# Adafruit_PA1010D_Mini_GPS.net
KiCad netlist of a schematic drawn in Altium Designer
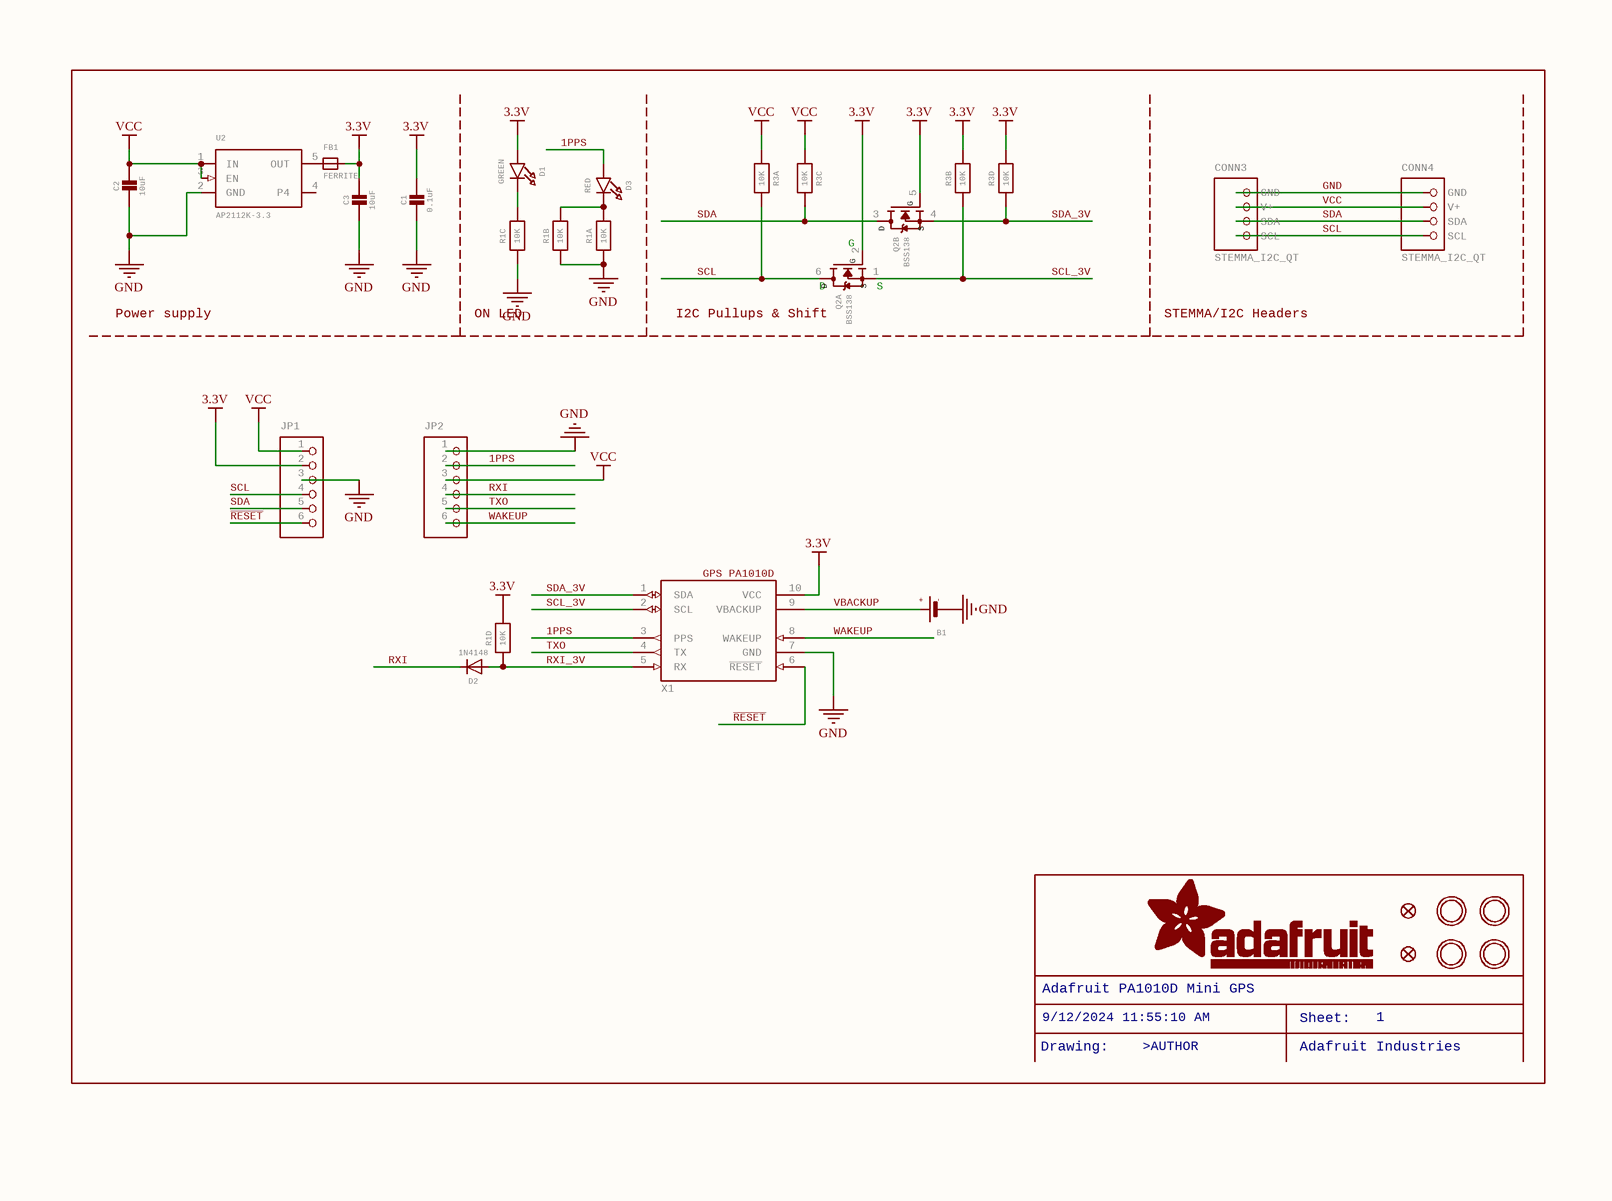
[diagram p0: Adafruit PA1010D Mini GPS.SchDoc]

(export (version "E")
  (design (tool "Eeschema 10.0.6"))
  (components
    (comp (ref "B1")
      (value "BATTERYCR1220_2")
      (footprint "CR1220-2")
      (description "CR1220 SMT - Digikey: 3001K-ND  CD2032 BAT-HLD-001 - Digikey: BAT-HLD-001-ND")
      (fields (field (name "+") "+") (field (name "-") "-"))
      (libsource (lib "microbuilder") (part "BATTERYCR1220_2"))
    )
    (comp (ref "C1")
      (value "0.1uF")
      (footprint "0603-NO")
      (libsource (lib "microbuilder") (part "CAP_CERAMIC0603_NO"))
    )
    (comp (ref "C2")
      (value "10uF")
      (footprint "0805-NO")
      (libsource (lib "microbuilder") (part "CAP_CERAMIC0805-NOOUTLINE"))
    )
    (comp (ref "C3")
      (value "10uF")
      (footprint "0805-NO")
      (libsource (lib "microbuilder") (part "CAP_CERAMIC0805-NOOUTLINE"))
    )
    (comp (ref "CONN3")
      (value "STEMMA_I2C_QT")
      (footprint "JST_SH4")
      (libsource (lib "microbuilder") (part "STEMMA_I2C_QT"))
    )
    (comp (ref "CONN4")
      (value "STEMMA_I2C_QT")
      (footprint "JST_SH4")
      (libsource (lib "microbuilder") (part "STEMMA_I2C_QT"))
    )
    (comp (ref "D1")
      (value "GREEN")
      (footprint "CHIPLED_0603_NOOUTLINE")
      (libsource (lib "microbuilder") (part "LED0603_NOOUTLINE"))
    )
    (comp (ref "D2")
      (value "1N4148")
      (footprint "SOD-323")
      (libsource (lib "microbuilder") (part "DIODESOD-323"))
    )
    (comp (ref "D3")
      (value "RED")
      (footprint "CHIPLED_0603_NOOUTLINE")
      (libsource (lib "microbuilder") (part "LED0603_NOOUTLINE"))
    )
    (comp (ref "FB1")
      (value "FERRITE")
      (footprint "0805-NO")
      (libsource (lib "microbuilder") (part "FERRITE-0805NO"))
    )
    (comp (ref "FID3")
      (value "FIDUCIAL_1MM")
      (footprint "FIDUCIAL_1MM")
      (description "Fiducial Alignment Points   Various fiducial points for machine vision alignment.")
      (libsource (lib "microbuilder") (part "FIDUCIAL_1MM"))
    )
    (comp (ref "FID4")
      (value "FIDUCIAL_1MM")
      (footprint "FIDUCIAL_1MM")
      (description "Fiducial Alignment Points   Various fiducial points for machine vision alignment.")
      (libsource (lib "microbuilder") (part "FIDUCIAL_1MM"))
    )
    (comp (ref "JP1")
      (value "HEADER-1X670MIL")
      (footprint "1X06_ROUND_70")
      (description "PIN HEADER")
      (libsource (lib "microbuilder") (part "HEADER-1X670MIL"))
    )
    (comp (ref "JP2")
      (value "HEADER-1X670MIL")
      (footprint "1X06_ROUND_70")
      (description "PIN HEADER")
      (libsource (lib "microbuilder") (part "HEADER-1X670MIL"))
    )
    (comp (ref "Q2")
      (value "BSS138")
      (footprint "SOT363")
      (description "Dual N-Channel MOSFET   SOT363 (2.0x1.25mm) 2N7002PS - 60V, 320mA [Digikey: 568-5984-1-ND]")
      (fields (field (name "D") "D") (field (name "S") "S") (field (name "G") "G"))
      (libsource (lib "microbuilder") (part "MOSFET-N_DUAL"))
    )
    (comp (ref "R1")
      (value "10K")
      (footprint "RESPACK_4X0603")
      (description "Resistor Packs (4 resistors)   4 x 0603 10K 1/16W - Digikey: YC164J-10KCT-ND")
      (libsource (lib "microbuilder") (part "RESISTOR_4PACK"))
    )
    (comp (ref "R3")
      (value "10K")
      (footprint "RESPACK_4X0603")
      (description "Resistor Packs (4 resistors)   4 x 0603 10K 1/16W - Digikey: YC164J-10KCT-ND")
      (libsource (lib "microbuilder") (part "RESISTOR_4PACK"))
    )
    (comp (ref "U$1")
      (value "MOUNTINGHOLE2.5")
      (footprint "MOUNTINGHOLE_2.5_PLATED")
      (description "Mounting Hole   For #2 screws (0.086\"/2.18mm width, 0.094\"/2.4mm hole) use 2.5mm")
      (libsource (lib "microbuilder") (part "MOUNTINGHOLE2.5"))
    )
    (comp (ref "U$17")
      (value "MOUNTINGHOLE2.5")
      (footprint "MOUNTINGHOLE_2.5_PLATED")
      (description "Mounting Hole   For #2 screws (0.086\"/2.18mm width, 0.094\"/2.4mm hole) use 2.5mm")
      (libsource (lib "microbuilder") (part "MOUNTINGHOLE2.5"))
    )
    (comp (ref "U$19")
      (value "MOUNTINGHOLE2.5")
      (footprint "MOUNTINGHOLE_2.5_PLATED")
      (description "Mounting Hole   For #2 screws (0.086\"/2.18mm width, 0.094\"/2.4mm hole) use 2.5mm")
      (libsource (lib "microbuilder") (part "MOUNTINGHOLE2.5"))
    )
    (comp (ref "U$21")
      (value "MOUNTINGHOLE2.5")
      (footprint "MOUNTINGHOLE_2.5_PLATED")
      (description "Mounting Hole   For #2 screws (0.086\"/2.18mm width, 0.094\"/2.4mm hole) use 2.5mm")
      (libsource (lib "microbuilder") (part "MOUNTINGHOLE2.5"))
    )
    (comp (ref "U2")
      (value "AP2112K-3.3")
      (footprint "SOT23-5")
      (libsource (lib "microbuilder") (part "VREG_SOT23-5"))
    )
    (comp (ref "X1")
      (value "GPS_PA1010D")
      (footprint "GPS_PA1010D")
      (fields (field (name "GPSPA1010D") "GPS PA1010D"))
      (libsource (lib "microbuilder") (part "GPS_PA1010D"))
    )
  )
  (nets
    (net (code "1") (name "/1PPS") (class "Default")
      (node (ref "D3") (pin "A") (pinfunction "A_A") (pintype "passive"))
      (node (ref "JP2") (pin "2") (pinfunction "2_2") (pintype "passive"))
      (node (ref "X1") (pin "3") (pinfunction "PPS_3") (pintype "output"))
    )
    (net (code "2") (name "/RXI") (class "Default")
      (node (ref "D2") (pin "C") (pinfunction "C_C") (pintype "passive"))
      (node (ref "JP2") (pin "4") (pinfunction "4_4") (pintype "passive"))
    )
    (net (code "3") (name "/RXI_3V") (class "Default")
      (node (ref "D2") (pin "A") (pinfunction "A_A") (pintype "passive"))
      (node (ref "R1") (pin "5") (pinfunction "2_5") (pintype "passive"))
      (node (ref "X1") (pin "5") (pinfunction "RX_5") (pintype "input"))
    )
    (net (code "4") (name "/SCL") (class "Default")
      (node (ref "CONN3") (pin "4") (pinfunction "SCL_4") (pintype "passive"))
      (node (ref "CONN4") (pin "4") (pinfunction "SCL_4") (pintype "passive"))
      (node (ref "JP1") (pin "4") (pinfunction "4_4") (pintype "passive"))
      (node (ref "Q2") (pin "6") (pinfunction "D_6") (pintype "bidirectional"))
      (node (ref "R3") (pin "8") (pinfunction "2_8") (pintype "passive"))
    )
    (net (code "5") (name "/SCL_3V") (class "Default")
      (node (ref "Q2") (pin "1") (pinfunction "S_1") (pintype "bidirectional"))
      (node (ref "R3") (pin "7") (pinfunction "2_7") (pintype "passive"))
      (node (ref "X1") (pin "2") (pinfunction "SCL_2") (pintype "bidirectional"))
    )
    (net (code "6") (name "/SDA") (class "Default")
      (node (ref "CONN3") (pin "3") (pinfunction "SDA_3") (pintype "passive"))
      (node (ref "CONN4") (pin "3") (pinfunction "SDA_3") (pintype "passive"))
      (node (ref "JP1") (pin "5") (pinfunction "5_5") (pintype "passive"))
      (node (ref "Q2") (pin "3") (pinfunction "D_3") (pintype "bidirectional"))
      (node (ref "R3") (pin "6") (pinfunction "2_6") (pintype "passive"))
    )
    (net (code "7") (name "/SDA_3V") (class "Default")
      (node (ref "Q2") (pin "4") (pinfunction "S_4") (pintype "bidirectional"))
      (node (ref "R3") (pin "5") (pinfunction "2_5") (pintype "passive"))
      (node (ref "X1") (pin "1") (pinfunction "SDA_1") (pintype "bidirectional"))
    )
    (net (code "8") (name "/TXO") (class "Default")
      (node (ref "JP2") (pin "5") (pinfunction "5_5") (pintype "passive"))
      (node (ref "X1") (pin "4") (pinfunction "TX_4") (pintype "output"))
    )
    (net (code "9") (name "/VBACKUP") (class "Default")
      (node (ref "B1") (pin "+") (pinfunction "+_+") (pintype "passive"))
      (node (ref "X1") (pin "9") (pinfunction "VBACKUP_9") (pintype "power_in"))
    )
    (net (code "10") (name "/WAKEUP") (class "Default")
      (node (ref "JP2") (pin "6") (pinfunction "6_6") (pintype "passive"))
      (node (ref "X1") (pin "8") (pinfunction "WAKEUP_8") (pintype "input"))
    )
    (net (code "11") (name "/~{RESET}") (class "Default")
      (node (ref "JP1") (pin "6") (pinfunction "6_6") (pintype "passive"))
      (node (ref "X1") (pin "6") (pinfunction "~{RESET}_6") (pintype "input"))
    )
    (net (code "12") (name "3.3V") (class "Default")
      (node (ref "C1") (pin "1") (pinfunction "1_1") (pintype "passive"))
      (node (ref "C3") (pin "1") (pinfunction "1_1") (pintype "passive"))
      (node (ref "D1") (pin "A") (pinfunction "A_A") (pintype "passive"))
      (node (ref "FB1") (pin "2") (pinfunction "P$2_2") (pintype "passive"))
      (node (ref "JP1") (pin "2") (pinfunction "2_2") (pintype "passive"))
      (node (ref "Q2") (pin "2") (pinfunction "G_2") (pintype "bidirectional"))
      (node (ref "Q2") (pin "5") (pinfunction "G_5") (pintype "bidirectional"))
      (node (ref "R1") (pin "4") (pinfunction "1_4") (pintype "passive"))
      (node (ref "R3") (pin "2") (pinfunction "1_2") (pintype "passive"))
      (node (ref "R3") (pin "4") (pinfunction "1_4") (pintype "passive"))
      (node (ref "X1") (pin "10") (pinfunction "VCC_10") (pintype "power_in"))
    )
    (net (code "13") (name "GND") (class "Default")
      (node (ref "B1") (pin "-") (pinfunction "-_-") (pintype "passive"))
      (node (ref "C1") (pin "2") (pinfunction "2_2") (pintype "passive"))
      (node (ref "C2") (pin "2") (pinfunction "2_2") (pintype "passive"))
      (node (ref "C3") (pin "2") (pinfunction "2_2") (pintype "passive"))
      (node (ref "CONN3") (pin "1") (pinfunction "GND_1") (pintype "passive"))
      (node (ref "CONN4") (pin "1") (pinfunction "GND_1") (pintype "passive"))
      (node (ref "JP1") (pin "3") (pinfunction "3_3") (pintype "passive"))
      (node (ref "JP2") (pin "1") (pinfunction "1_1") (pintype "passive"))
      (node (ref "R1") (pin "1") (pinfunction "1_1") (pintype "passive"))
      (node (ref "R1") (pin "2") (pinfunction "1_2") (pintype "passive"))
      (node (ref "R1") (pin "3") (pinfunction "1_3") (pintype "passive"))
      (node (ref "U2") (pin "2") (pinfunction "GND_2") (pintype "power_in"))
      (node (ref "X1") (pin "7") (pinfunction "GND_7") (pintype "power_in"))
    )
    (net (code "14") (name "Net-(FB1-P$1)") (class "Default")
      (node (ref "FB1") (pin "1") (pinfunction "P$1_1") (pintype "passive"))
      (node (ref "U2") (pin "5") (pinfunction "OUT_5") (pintype "power_in"))
    )
    (net (code "15") (name "Net-(R1A-2)") (class "Default")
      (node (ref "D3") (pin "C") (pinfunction "C_C") (pintype "passive"))
      (node (ref "R1") (pin "7") (pinfunction "2_7") (pintype "passive"))
      (node (ref "R1") (pin "8") (pinfunction "2_8") (pintype "passive"))
    )
    (net (code "16") (name "Net-(R1C-2)") (class "Default")
      (node (ref "D1") (pin "C") (pinfunction "C_C") (pintype "passive"))
      (node (ref "R1") (pin "6") (pinfunction "2_6") (pintype "passive"))
    )
    (net (code "17") (name "VCC") (class "Default")
      (node (ref "C2") (pin "1") (pinfunction "1_1") (pintype "passive"))
      (node (ref "CONN3") (pin "2") (pinfunction "V+_2") (pintype "passive"))
      (node (ref "CONN4") (pin "2") (pinfunction "V+_2") (pintype "passive"))
      (node (ref "JP1") (pin "1") (pinfunction "1_1") (pintype "passive"))
      (node (ref "JP2") (pin "3") (pinfunction "3_3") (pintype "passive"))
      (node (ref "R3") (pin "1") (pinfunction "1_1") (pintype "passive"))
      (node (ref "R3") (pin "3") (pinfunction "1_3") (pintype "passive"))
      (node (ref "U2") (pin "1") (pinfunction "IN_1") (pintype "power_in"))
      (node (ref "U2") (pin "3") (pinfunction "EN_3") (pintype "input"))
    )
    (net (code "18") (name "unconnected-(U2-P4-Pad4)") (class "Default")
      (node (ref "U2") (pin "4") (pinfunction "P4_4") (pintype "bidirectional"))
    )
  )
)
